# 02_-STLinkV2_1.net
KiCad netlist of a schematic drawn in Altium Designer
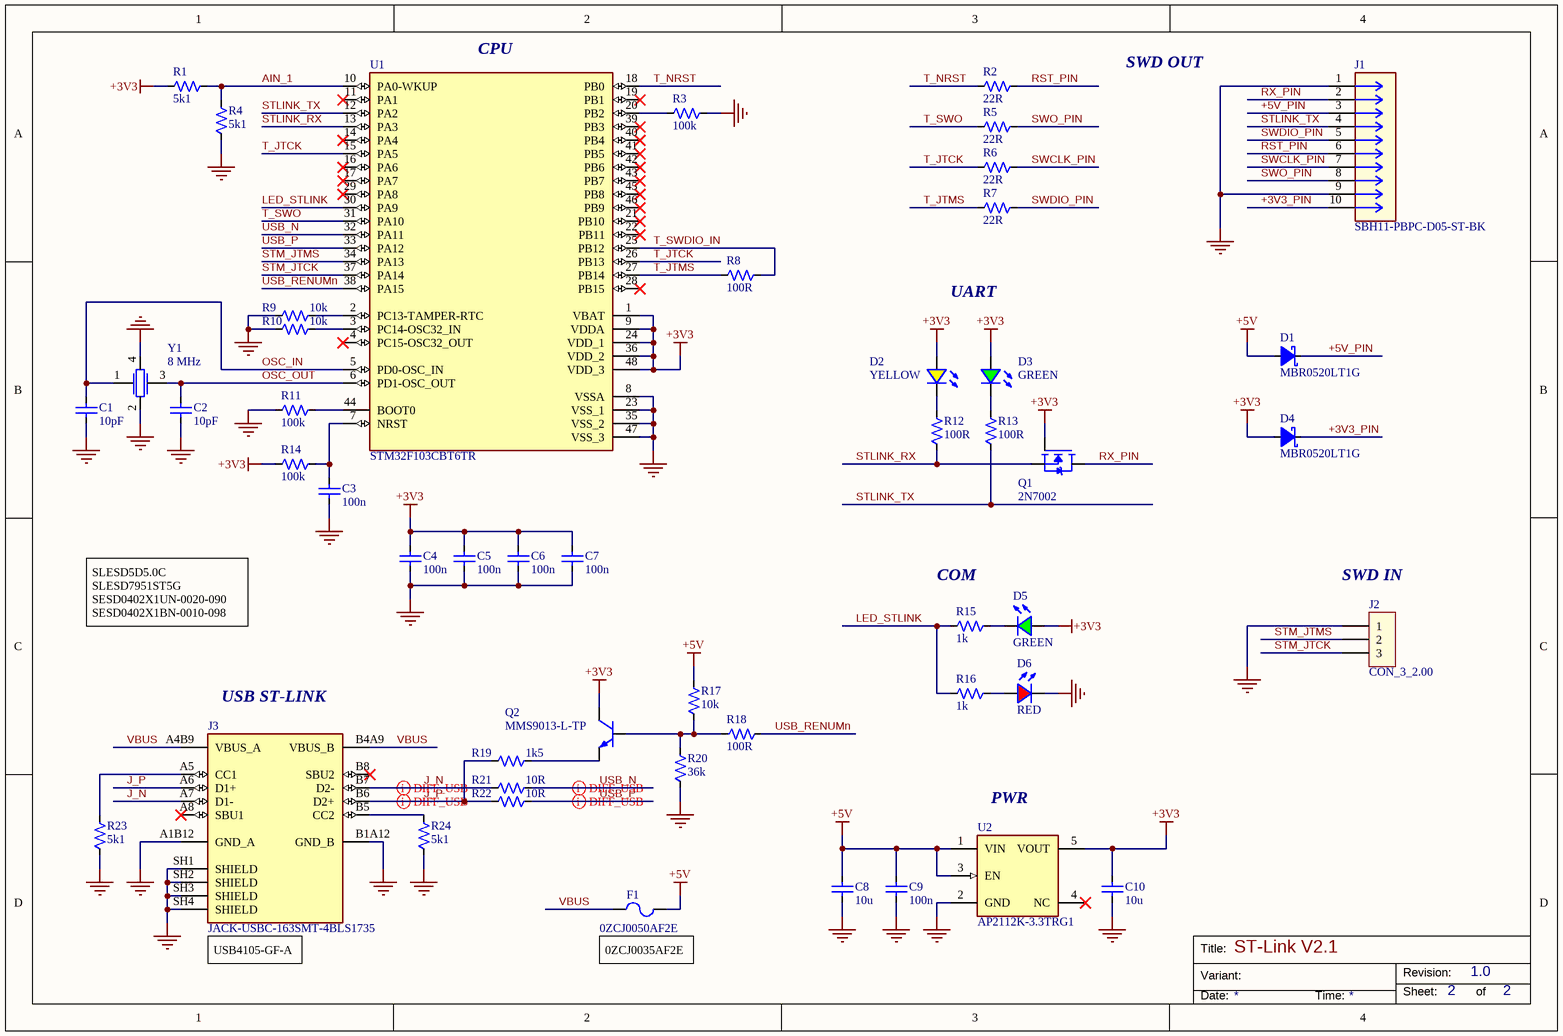
[diagram p0: [02]-STLinkV2_1.SchDoc]

(export (version "E")
  (design (tool "Eeschema 10.0.6"))
  (components
    (comp (ref "C1")
      (value "10pF")
      (footprint "CAPC1005X55N")
      (description "50V 10pF C0G ±5% 0402 Multilayer Ceramic Capacitors MLCC - SMD/SMT ROHS")
      (fields (field (name "TOLERANCE") "5%"))
      (libsource (lib "STLinkV2_1") (part "CAP_GCM1555C1H100JA16D"))
    )
    (comp (ref "C2")
      (value "10pF")
      (footprint "CAPC1005X55N")
      (description "50V 10pF C0G ±5% 0402 Multilayer Ceramic Capacitors MLCC - SMD/SMT ROHS")
      (fields (field (name "TOLERANCE") "5%"))
      (libsource (lib "STLinkV2_1") (part "CAP_GCM1555C1H100JA16D"))
    )
    (comp (ref "C3")
      (value "100n")
      (footprint "CAPC1005X55N")
      (description "50V 100nF X7R ±10% 0402 Multilayer Ceramic Capacitors MLCC - SMD/SMT ROHS")
      (fields (field (name "TOLERANCE") "10%"))
      (libsource (lib "STLinkV2_1") (part "CAP_GCM155R71H104KE02D"))
    )
    (comp (ref "C4")
      (value "100n")
      (footprint "CAPC1005X55N")
      (description "50V 100nF X7R ±10% 0402 Multilayer Ceramic Capacitors MLCC - SMD/SMT ROHS")
      (fields (field (name "TOLERANCE") "10%"))
      (libsource (lib "STLinkV2_1") (part "CAP_GCM155R71H104KE02D"))
    )
    (comp (ref "C5")
      (value "100n")
      (footprint "CAPC1005X55N")
      (description "50V 100nF X7R ±10% 0402 Multilayer Ceramic Capacitors MLCC - SMD/SMT ROHS")
      (fields (field (name "TOLERANCE") "10%"))
      (libsource (lib "STLinkV2_1") (part "CAP_GCM155R71H104KE02D"))
    )
    (comp (ref "C6")
      (value "100n")
      (footprint "CAPC1005X55N")
      (description "50V 100nF X7R ±10% 0402 Multilayer Ceramic Capacitors MLCC - SMD/SMT ROHS")
      (fields (field (name "TOLERANCE") "10%"))
      (libsource (lib "STLinkV2_1") (part "CAP_GCM155R71H104KE02D"))
    )
    (comp (ref "C7")
      (value "100n")
      (footprint "CAPC1005X55N")
      (description "50V 100nF X7R ±10% 0402 Multilayer Ceramic Capacitors MLCC - SMD/SMT ROHS")
      (fields (field (name "TOLERANCE") "10%"))
      (libsource (lib "STLinkV2_1") (part "CAP_GCM155R71H104KE02D"))
    )
    (comp (ref "C8")
      (value "10u")
      (footprint "CAPC0603(1608Metric)L")
      (description "10 µF ±20% 16V Ceramic Capacitor X6S 0603 (1608 Metric)")
      (fields (field (name "TOLERANCE") "20%") (field (name "VOLTAGE") "16V"))
      (libsource (lib "STLinkV2_1") (part "CAP_GRM188C81C106MA73D"))
    )
    (comp (ref "C9")
      (value "100n")
      (footprint "CAPC1005X55N")
      (description "50V 100nF X7R ±10% 0402 Multilayer Ceramic Capacitors MLCC - SMD/SMT ROHS")
      (fields (field (name "TOLERANCE") "10%"))
      (libsource (lib "STLinkV2_1") (part "CAP_GCM155R71H104KE02D"))
    )
    (comp (ref "C10")
      (value "10u")
      (footprint "CAPC0603(1608Metric)L")
      (description "10 µF ±20% 16V Ceramic Capacitor X6S 0603 (1608 Metric)")
      (fields (field (name "TOLERANCE") "20%") (field (name "VOLTAGE") "16V"))
      (libsource (lib "STLinkV2_1") (part "CAP_GRM188C81C106MA73D"))
    )
    (comp (ref "D1")
      (value "MBR0520LT1G")
      (footprint "SOD3716X135N")
      (description "Diode, Schottky Barrier, Vr 20V, If 0.5A, Pkg SOD-123, Vf 0.385V, Tj +125DEGC, Cs 5.5A")
      (libsource (lib "STLinkV2_1") (part "MBR0520LT1G"))
    )
    (comp (ref "D2")
      (value "YELLOW")
      (footprint "WL-SMCW_0603_150060xx75003")
      (description "Led, Yellow, 550Mcd, 595Nm Rohs Compliant: Yes")
      (libsource (lib "STLinkV2_1") (part "150060YS75003"))
    )
    (comp (ref "D3")
      (value "GREEN")
      (footprint "WL-SMCW_0603_150060xx75003")
      (description "Led, Bright Green, 100Mcd, 572Nm Rohs Compliant: Yes")
      (libsource (lib "STLinkV2_1") (part "150060VS75003"))
    )
    (comp (ref "D4")
      (value "MBR0520LT1G")
      (footprint "SOD3716X135N")
      (description "Diode, Schottky Barrier, Vr 20V, If 0.5A, Pkg SOD-123, Vf 0.385V, Tj +125DEGC, Cs 5.5A")
      (libsource (lib "STLinkV2_1") (part "MBR0520LT1G"))
    )
    (comp (ref "D5")
      (value "GREEN")
      (footprint "WL-SMCW_0603_150060xx75003")
      (description "Led, Bright Green, 100Mcd, 572Nm Rohs Compliant: Yes")
      (libsource (lib "STLinkV2_1") (part "150060VS75003"))
    )
    (comp (ref "D6")
      (value "RED")
      (description "SMT Mono-Color Chip LED Waterclear Advance WL-SMCW_0603_ADVANCE")
      (libsource (lib "STLinkV2_1") (part "150060RS75003"))
    )
    (comp (ref "F1")
      (value "0ZCJ0050AF2E")
      (footprint "0ZCJ_BEL")
      (description "Resettable Fuse, PPTC, 1206 (3216 Metric), 0ZCJ Series, 24 VDC, 500 mA, 1 A, 0.1 s")
      (libsource (lib "STLinkV2_1") (part "0ZCJ0050AF2E"))
    )
    (comp (ref "J1")
      (value "SBH11-PBPC-D05-ST-BK")
      (footprint "SULLINS_SBH11-PBPC-D05-ST-BK-H")
      (description "Conn Shrouded Header (4 Sides) HDR 10 POS 2.54mm Solder ST Top Entry Thru-Hole")
      (libsource (lib "STLinkV2_1") (part "SBH11-PBPC-D05-ST-BK"))
    )
    (comp (ref "J2")
      (value "CON_3_2.00")
      (footprint "Pin3")
      (libsource (lib "STLinkV2_1") (part "CON_3_2.00"))
    )
    (comp (ref "J3")
      (value "JACK-USBC-163SMT-4BLS1735")
      (footprint "JACK-USBC-163SMT-4BLS1735")
      (description "Usb Type C Jack IPX7 SMT")
      (libsource (lib "STLinkV2_1") (part "JACK-USBC-163SMT-4BLS1735"))
    )
    (comp (ref "Q1")
      (value "2N7002")
      (footprint "SOT23-3")
      (description "MOSFET N-CH 60V 300MA SOT23-3 N-Channel 60 V 300mA (Ta) 500mW (Ta) Surface Mount PG-SOT23")
      (libsource (lib "STLinkV2_1") (part "2N7002H6327XTSA2"))
    )
    (comp (ref "Q2")
      (value "MMS9013-L-TP")
      (footprint "SOT23-3")
      (description "Small Signal Bipolar Transistor, 0.5A I(C), 25V V(BR)CEO, 1-Element, NPN, Silicon")
      (libsource (lib "STLinkV2_1") (part "MMS9013-L-TP"))
    )
    (comp (ref "R1")
      (value "5k1")
      (footprint "RESC1005X37N")
      (description "Res Thick Film 0402 5.1K Ohm 1% 0.063W(1/16W) ±100ppm/°C Pad SMD T/R Automotive AEC-Q200")
      (fields (field (name "TOLERANCE") "1%"))
      (libsource (lib "STLinkV2_1") (part "RES_AC0402FR-135K1L"))
    )
    (comp (ref "R2")
      (value "22R")
      (footprint "RESC1005X37N")
      (description "125mW Thick Film Resistors ±100ppm/℃ ±1% 22Ω 0402 Chip Resistor - Surface Mount ROHS")
      (fields (field (name "TOLERANCE") "1%"))
      (libsource (lib "STLinkV2_1") (part "RES_AC0402FR-7W22RL"))
    )
    (comp (ref "R3")
      (value "100k")
      (footprint "RESC1005X37N")
      (description "Res Thick Film 0402 100K Ohm 1% 0.125W(1/8W) ±100ppm/°C Pad SMD T/R Automotive AEC-Q200")
      (fields (field (name "TOLERANCE") "1%"))
      (libsource (lib "STLinkV2_1") (part "RES_AC0402FR-7W100KL"))
    )
    (comp (ref "R4")
      (value "5k1")
      (footprint "RESC1005X37N")
      (description "Res Thick Film 0402 5.1K Ohm 1% 0.063W(1/16W) ±100ppm/°C Pad SMD T/R Automotive AEC-Q200")
      (fields (field (name "TOLERANCE") "1%"))
      (libsource (lib "STLinkV2_1") (part "RES_AC0402FR-135K1L"))
    )
    (comp (ref "R5")
      (value "22R")
      (footprint "RESC1005X37N")
      (description "125mW Thick Film Resistors ±100ppm/℃ ±1% 22Ω 0402 Chip Resistor - Surface Mount ROHS")
      (fields (field (name "TOLERANCE") "1%"))
      (libsource (lib "STLinkV2_1") (part "RES_AC0402FR-7W22RL"))
    )
    (comp (ref "R6")
      (value "22R")
      (footprint "RESC1005X37N")
      (description "125mW Thick Film Resistors ±100ppm/℃ ±1% 22Ω 0402 Chip Resistor - Surface Mount ROHS")
      (fields (field (name "TOLERANCE") "1%"))
      (libsource (lib "STLinkV2_1") (part "RES_AC0402FR-7W22RL"))
    )
    (comp (ref "R7")
      (value "22R")
      (footprint "RESC1005X37N")
      (description "125mW Thick Film Resistors ±100ppm/℃ ±1% 22Ω 0402 Chip Resistor - Surface Mount ROHS")
      (fields (field (name "TOLERANCE") "1%"))
      (libsource (lib "STLinkV2_1") (part "RES_AC0402FR-7W22RL"))
    )
    (comp (ref "R8")
      (value "100R")
      (footprint "RESC1005X37N")
      (description "Res Thick Film 0402 100 Ohm 1% 0.125W(1/8W) ±100ppm/C Pad SMD T/R Automotive AEC-Q200")
      (fields (field (name "TOLERANCE") "1%"))
      (libsource (lib "STLinkV2_1") (part "RES_AC0402FR-7W100RL"))
    )
    (comp (ref "R9")
      (value "10k")
      (footprint "RESC1005X37N")
      (description "Res Thick Film 0402 10K Ohm 1% 0.125W(1/8W) ±100ppm/C Pad SMD Automotive T/R")
      (fields (field (name "TOLERANCE") "1%"))
      (libsource (lib "STLinkV2_1") (part "RES_AC0402FR-7W10KL"))
    )
    (comp (ref "R10")
      (value "10k")
      (footprint "RESC1005X37N")
      (description "Res Thick Film 0402 10K Ohm 1% 0.125W(1/8W) ±100ppm/C Pad SMD Automotive T/R")
      (fields (field (name "TOLERANCE") "1%"))
      (libsource (lib "STLinkV2_1") (part "RES_AC0402FR-7W10KL"))
    )
    (comp (ref "R11")
      (value "100k")
      (footprint "RESC1005X37N")
      (description "Res Thick Film 0402 100K Ohm 1% 0.125W(1/8W) ±100ppm/°C Pad SMD T/R Automotive AEC-Q200")
      (fields (field (name "TOLERANCE") "1%"))
      (libsource (lib "STLinkV2_1") (part "RES_AC0402FR-7W100KL"))
    )
    (comp (ref "R12")
      (value "100R")
      (footprint "RESC1005X37N")
      (description "Res Thick Film 0402 100 Ohm 1% 0.125W(1/8W) ±100ppm/C Pad SMD T/R Automotive AEC-Q200")
      (fields (field (name "TOLERANCE") "1%"))
      (libsource (lib "STLinkV2_1") (part "RES_AC0402FR-7W100RL"))
    )
    (comp (ref "R13")
      (value "100R")
      (footprint "RESC1005X37N")
      (description "Res Thick Film 0402 100 Ohm 1% 0.125W(1/8W) ±100ppm/C Pad SMD T/R Automotive AEC-Q200")
      (fields (field (name "TOLERANCE") "1%"))
      (libsource (lib "STLinkV2_1") (part "RES_AC0402FR-7W100RL"))
    )
    (comp (ref "R14")
      (value "100k")
      (footprint "RESC1005X37N")
      (description "Res Thick Film 0402 100K Ohm 1% 0.125W(1/8W) ±100ppm/°C Pad SMD T/R Automotive AEC-Q200")
      (fields (field (name "TOLERANCE") "1%"))
      (libsource (lib "STLinkV2_1") (part "RES_AC0402FR-7W100KL"))
    )
    (comp (ref "R15")
      (value "1k")
      (footprint "RESC1005X37N")
      (description "Res Thick Film 0402 1K Ohm 1% 0.125W(1/8W) ±100ppm/C Pad SMD Automotive T/R")
      (fields (field (name "TOLERANCE") "1%"))
      (libsource (lib "STLinkV2_1") (part "RES_AC0402FR-7W1KL"))
    )
    (comp (ref "R16")
      (value "1k")
      (footprint "RESC1005X37N")
      (description "Res Thick Film 0402 1K Ohm 1% 0.125W(1/8W) ±100ppm/C Pad SMD Automotive T/R")
      (fields (field (name "TOLERANCE") "1%"))
      (libsource (lib "STLinkV2_1") (part "RES_AC0402FR-7W1KL"))
    )
    (comp (ref "R17")
      (value "10k")
      (footprint "RESC1005X37N")
      (description "Res Thick Film 0402 10K Ohm 1% 0.125W(1/8W) ±100ppm/C Pad SMD Automotive T/R")
      (fields (field (name "TOLERANCE") "1%"))
      (libsource (lib "STLinkV2_1") (part "RES_AC0402FR-7W10KL"))
    )
    (comp (ref "R18")
      (value "100R")
      (footprint "RESC1005X37N")
      (description "Res Thick Film 0402 100 Ohm 1% 0.125W(1/8W) ±100ppm/C Pad SMD T/R Automotive AEC-Q200")
      (fields (field (name "TOLERANCE") "1%"))
      (libsource (lib "STLinkV2_1") (part "RES_AC0402FR-7W100RL"))
    )
    (comp (ref "R19")
      (value "1k5")
      (footprint "RESC1005X37N")
      (fields (field (name "TOLERANCE") "1%"))
      (libsource (lib "STLinkV2_1") (part "RES_AC0402FR-7W1K5L"))
    )
    (comp (ref "R20")
      (value "36k")
      (footprint "RESC1005X37N")
      (description "Chip Resistor Automotive Grade Thick Film 0402 36kOhm 1% Paper T/R")
      (fields (field (name "TOLERANCE") "1%"))
      (libsource (lib "STLinkV2_1") (part "RES_AC0402FR-7W36KL"))
    )
    (comp (ref "R21")
      (value "10R")
      (footprint "RESC1005X37N")
      (description "Res Thick Film 0402 10 Ohm 1% 0.125W(1/8W) ±100ppm/C Pad SMD T/R Automotive AEC-Q200")
      (fields (field (name "TOLERANCE") "1%"))
      (libsource (lib "STLinkV2_1") (part "RES_AC0402FR-7W10RL"))
    )
    (comp (ref "R22")
      (value "10R")
      (footprint "RESC1005X37N")
      (description "Res Thick Film 0402 10 Ohm 1% 0.125W(1/8W) ±100ppm/C Pad SMD T/R Automotive AEC-Q200")
      (fields (field (name "TOLERANCE") "1%"))
      (libsource (lib "STLinkV2_1") (part "RES_AC0402FR-7W10RL"))
    )
    (comp (ref "R23")
      (value "5k1")
      (footprint "RESC1005X37N")
      (description "Res Thick Film 0402 5.1K Ohm 1% 0.063W(1/16W) ±100ppm/°C Pad SMD T/R Automotive AEC-Q200")
      (fields (field (name "TOLERANCE") "1%"))
      (libsource (lib "STLinkV2_1") (part "RES_AC0402FR-135K1L"))
    )
    (comp (ref "R24")
      (value "5k1")
      (footprint "RESC1005X37N")
      (description "Res Thick Film 0402 5.1K Ohm 1% 0.063W(1/16W) ±100ppm/°C Pad SMD T/R Automotive AEC-Q200")
      (fields (field (name "TOLERANCE") "1%"))
      (libsource (lib "STLinkV2_1") (part "RES_AC0402FR-135K1L"))
    )
    (comp (ref "U1")
      (value "STM32F103CBT6TR")
      (footprint "QFP50P900X900X160-48N")
      (description "MCU 32-bit STM32F1 ARM Cortex M3 RISC 128KB Flash 2.5V/3.3V 48-Pin LQFP T/R")
      (libsource (lib "STLinkV2_1") (part "STM32F103CBT6TR"))
    )
    (comp (ref "U2")
      (value "AP2112K-3.3TRG1")
      (footprint "SOT95P285X140-5N")
      (description "AP2112 Series 0.6 A 3.3 V Fixed Output SMT LDO Linear Regulator - SOT23-5")
      (libsource (lib "STLinkV2_1") (part "AP2112K-3.3TRG1"))
    )
    (comp (ref "Y1")
      (value "8 MHz")
      (footprint "XTAL_C3E-8.000-8-1015-R")
      (description "CRYSTAL 8.0000MHZ 10PF SMD")
      (fields (field (name "MFG") "ECS Inc.") (field (name "MFG PART NUMBER") "ECS-80-10-33-CKM-TR3"))
      (libsource (lib "STLinkV2_1") (part "Y_ECS-80-10-33-CKM-TR3"))
    )
  )
  (nets
    (net (code "1") (name "+3V3") (class "Default")
      (node (ref "C10") (pin "2") (pinfunction "2_2") (pintype "passive"))
      (node (ref "C4") (pin "1") (pinfunction "1_1") (pintype "passive"))
      (node (ref "C5") (pin "1") (pinfunction "1_1") (pintype "passive"))
      (node (ref "C6") (pin "1") (pinfunction "1_1") (pintype "passive"))
      (node (ref "C7") (pin "1") (pinfunction "1_1") (pintype "passive"))
      (node (ref "D2") (pin "1") (pinfunction "POS_1") (pintype "passive"))
      (node (ref "D3") (pin "1") (pinfunction "POS_1") (pintype "passive"))
      (node (ref "D4") (pin "1") (pinfunction "A_1") (pintype "passive"))
      (node (ref "D5") (pin "1") (pinfunction "POS_1") (pintype "passive"))
      (node (ref "Q1") (pin "1") (pinfunction "G_1") (pintype "passive"))
      (node (ref "Q2") (pin "3") (pinfunction "C_3") (pintype "passive"))
      (node (ref "R1") (pin "2") (pinfunction "2_2") (pintype "passive"))
      (node (ref "R14") (pin "2") (pinfunction "2_2") (pintype "passive"))
      (node (ref "U1") (pin "1") (pinfunction "VBAT_1") (pintype "power_in"))
      (node (ref "U1") (pin "24") (pinfunction "VDD_1_24") (pintype "power_in"))
      (node (ref "U1") (pin "36") (pinfunction "VDD_2_36") (pintype "power_in"))
      (node (ref "U1") (pin "48") (pinfunction "VDD_3_48") (pintype "power_in"))
      (node (ref "U1") (pin "9") (pinfunction "VDDA_9") (pintype "power_in"))
      (node (ref "U2") (pin "5") (pinfunction "VOUT_5") (pintype "power_in"))
    )
    (net (code "2") (name "+5V") (class "Default")
      (node (ref "C8") (pin "2") (pinfunction "2_2") (pintype "passive"))
      (node (ref "C9") (pin "1") (pinfunction "1_1") (pintype "passive"))
      (node (ref "D1") (pin "1") (pinfunction "A_1") (pintype "passive"))
      (node (ref "F1") (pin "2") (pinfunction "2_2") (pintype "passive"))
      (node (ref "R17") (pin "1") (pinfunction "1_1") (pintype "passive"))
      (node (ref "U2") (pin "1") (pinfunction "VIN_1") (pintype "power_in"))
      (node (ref "U2") (pin "3") (pinfunction "EN_3") (pintype "input"))
    )
    (net (code "3") (name "/+3V3_PIN") (class "Default")
      (node (ref "D4") (pin "2") (pinfunction "K_2") (pintype "passive"))
      (node (ref "J1") (pin "10") (pinfunction "10_10") (pintype "passive"))
    )
    (net (code "4") (name "/+5V_PIN") (class "Default")
      (node (ref "D1") (pin "2") (pinfunction "K_2") (pintype "passive"))
      (node (ref "J1") (pin "3") (pinfunction "3_3") (pintype "passive"))
    )
    (net (code "5") (name "/AIN_1") (class "Default")
      (node (ref "R1") (pin "1") (pinfunction "1_1") (pintype "passive"))
      (node (ref "R4") (pin "1") (pinfunction "1_1") (pintype "passive"))
      (node (ref "U1") (pin "10") (pinfunction "PA0-WKUP_10") (pintype "bidirectional"))
    )
    (net (code "6") (name "/J_N") (class "Default")
      (node (ref "J3") (pin "A7") (pinfunction "D1-_A7") (pintype "bidirectional"))
      (node (ref "J3") (pin "B7") (pinfunction "D2-_B7") (pintype "bidirectional"))
      (node (ref "R21") (pin "2") (pinfunction "2_2") (pintype "passive"))
    )
    (net (code "7") (name "/J_P") (class "Default")
      (node (ref "J3") (pin "A6") (pinfunction "D1+_A6") (pintype "bidirectional"))
      (node (ref "J3") (pin "B6") (pinfunction "D2+_B6") (pintype "bidirectional"))
      (node (ref "R19") (pin "2") (pinfunction "2_2") (pintype "passive"))
      (node (ref "R22") (pin "2") (pinfunction "2_2") (pintype "passive"))
    )
    (net (code "8") (name "/LED_STLINK") (class "Default")
      (node (ref "R15") (pin "2") (pinfunction "2_2") (pintype "passive"))
      (node (ref "R16") (pin "2") (pinfunction "2_2") (pintype "passive"))
      (node (ref "U1") (pin "30") (pinfunction "PA9_30") (pintype "bidirectional"))
    )
    (net (code "9") (name "/OSC_IN") (class "Default")
      (node (ref "C1") (pin "2") (pinfunction "2_2") (pintype "passive"))
      (node (ref "U1") (pin "5") (pinfunction "PD0-OSC_IN_5") (pintype "bidirectional"))
      (node (ref "Y1") (pin "1") (pinfunction "1_1") (pintype "passive"))
    )
    (net (code "10") (name "/OSC_OUT") (class "Default")
      (node (ref "C2") (pin "2") (pinfunction "2_2") (pintype "passive"))
      (node (ref "U1") (pin "6") (pinfunction "PD1-OSC_OUT_6") (pintype "bidirectional"))
      (node (ref "Y1") (pin "3") (pinfunction "2_3") (pintype "passive"))
    )
    (net (code "11") (name "/RST_PIN") (class "Default")
      (node (ref "J1") (pin "6") (pinfunction "6_6") (pintype "passive"))
      (node (ref "R2") (pin "1") (pinfunction "1_1") (pintype "passive"))
    )
    (net (code "12") (name "/RX_PIN") (class "Default")
      (node (ref "J1") (pin "2") (pinfunction "2_2") (pintype "passive"))
      (node (ref "Q1") (pin "3") (pinfunction "D_3") (pintype "passive"))
    )
    (net (code "13") (name "/STLINK_RX") (class "Default")
      (node (ref "Q1") (pin "2") (pinfunction "S_2") (pintype "passive"))
      (node (ref "R12") (pin "2") (pinfunction "2_2") (pintype "passive"))
      (node (ref "U1") (pin "13") (pinfunction "PA3_13") (pintype "bidirectional"))
    )
    (net (code "14") (name "/STLINK_TX") (class "Default")
      (node (ref "J1") (pin "4") (pinfunction "4_4") (pintype "passive"))
      (node (ref "R13") (pin "2") (pinfunction "2_2") (pintype "passive"))
      (node (ref "U1") (pin "12") (pinfunction "PA2_12") (pintype "bidirectional"))
    )
    (net (code "15") (name "/STM_JTCK") (class "Default")
      (node (ref "J2") (pin "3") (pinfunction "3_3") (pintype "passive"))
      (node (ref "U1") (pin "37") (pinfunction "PA14_37") (pintype "bidirectional"))
    )
    (net (code "16") (name "/STM_JTMS") (class "Default")
      (node (ref "J2") (pin "2") (pinfunction "2_2") (pintype "passive"))
      (node (ref "U1") (pin "34") (pinfunction "PA13_34") (pintype "bidirectional"))
    )
    (net (code "17") (name "/SWCLK_PIN") (class "Default")
      (node (ref "J1") (pin "7") (pinfunction "7_7") (pintype "passive"))
      (node (ref "R6") (pin "1") (pinfunction "1_1") (pintype "passive"))
    )
    (net (code "18") (name "/SWDIO_PIN") (class "Default")
      (node (ref "J1") (pin "5") (pinfunction "5_5") (pintype "passive"))
      (node (ref "R7") (pin "1") (pinfunction "1_1") (pintype "passive"))
    )
    (net (code "19") (name "/SWO_PIN") (class "Default")
      (node (ref "J1") (pin "8") (pinfunction "8_8") (pintype "passive"))
      (node (ref "R5") (pin "1") (pinfunction "1_1") (pintype "passive"))
    )
    (net (code "20") (name "/T_JTCK") (class "Default")
      (node (ref "R6") (pin "2") (pinfunction "2_2") (pintype "passive"))
      (node (ref "U1") (pin "15") (pinfunction "PA5_15") (pintype "bidirectional"))
      (node (ref "U1") (pin "26") (pinfunction "PB13_26") (pintype "bidirectional"))
    )
    (net (code "21") (name "/T_JTMS") (class "Default")
      (node (ref "R7") (pin "2") (pinfunction "2_2") (pintype "passive"))
      (node (ref "R8") (pin "2") (pinfunction "2_2") (pintype "passive"))
      (node (ref "U1") (pin "27") (pinfunction "PB14_27") (pintype "bidirectional"))
    )
    (net (code "22") (name "/T_NRST") (class "Default")
      (node (ref "R2") (pin "2") (pinfunction "2_2") (pintype "passive"))
      (node (ref "U1") (pin "18") (pinfunction "PB0_18") (pintype "bidirectional"))
    )
    (net (code "23") (name "/T_SWDIO_IN") (class "Default")
      (node (ref "R8") (pin "1") (pinfunction "1_1") (pintype "passive"))
      (node (ref "U1") (pin "25") (pinfunction "PB12_25") (pintype "bidirectional"))
    )
    (net (code "24") (name "/T_SWO") (class "Default")
      (node (ref "R5") (pin "2") (pinfunction "2_2") (pintype "passive"))
      (node (ref "U1") (pin "31") (pinfunction "PA10_31") (pintype "bidirectional"))
    )
    (net (code "25") (name "/USB_N") (class "Default")
      (node (ref "R21") (pin "1") (pinfunction "1_1") (pintype "passive"))
      (node (ref "U1") (pin "32") (pinfunction "PA11_32") (pintype "bidirectional"))
    )
    (net (code "26") (name "/USB_P") (class "Default")
      (node (ref "R22") (pin "1") (pinfunction "1_1") (pintype "passive"))
      (node (ref "U1") (pin "33") (pinfunction "PA12_33") (pintype "bidirectional"))
    )
    (net (code "27") (name "/USB_RENUMn") (class "Default")
      (node (ref "R18") (pin "2") (pinfunction "2_2") (pintype "passive"))
      (node (ref "U1") (pin "38") (pinfunction "PA15_38") (pintype "bidirectional"))
    )
    (net (code "28") (name "/VBUS") (class "Default")
      (node (ref "F1") (pin "1") (pinfunction "1_1") (pintype "passive"))
      (node (ref "J3") (pin "A4B9") (pinfunction "VBUS_A_A4B9") (pintype "power_in"))
      (node (ref "J3") (pin "B4A9") (pinfunction "VBUS_B_B4A9") (pintype "power_in"))
    )
    (net (code "29") (name "GND") (class "Default")
      (node (ref "C1") (pin "1") (pinfunction "1_1") (pintype "passive"))
      (node (ref "C10") (pin "1") (pinfunction "1_1") (pintype "passive"))
      (node (ref "C2") (pin "1") (pinfunction "1_1") (pintype "passive"))
      (node (ref "C3") (pin "2") (pinfunction "2_2") (pintype "passive"))
      (node (ref "C4") (pin "2") (pinfunction "2_2") (pintype "passive"))
      (node (ref "C5") (pin "2") (pinfunction "2_2") (pintype "passive"))
      (node (ref "C6") (pin "2") (pinfunction "2_2") (pintype "passive"))
      (node (ref "C7") (pin "2") (pinfunction "2_2") (pintype "passive"))
      (node (ref "C8") (pin "1") (pinfunction "1_1") (pintype "passive"))
      (node (ref "C9") (pin "2") (pinfunction "2_2") (pintype "passive"))
      (node (ref "D6") (pin "2") (pinfunction "NEG_2") (pintype "passive"))
      (node (ref "J1") (pin "1") (pinfunction "1_1") (pintype "passive"))
      (node (ref "J1") (pin "9") (pinfunction "9_9") (pintype "passive"))
      (node (ref "J2") (pin "1") (pinfunction "1_1") (pintype "passive"))
      (node (ref "J3") (pin "A1B12") (pinfunction "GND_A_A1B12") (pintype "power_in"))
      (node (ref "J3") (pin "B1A12") (pinfunction "GND_B_B1A12") (pintype "power_in"))
      (node (ref "J3") (pin "SH1") (pinfunction "SHIELD_SH1") (pintype "passive"))
      (node (ref "J3") (pin "SH2") (pinfunction "SHIELD_SH2") (pintype "passive"))
      (node (ref "J3") (pin "SH3") (pinfunction "SHIELD_SH3") (pintype "passive"))
      (node (ref "J3") (pin "SH4") (pinfunction "SHIELD_SH4") (pintype "passive"))
      (node (ref "R10") (pin "2") (pinfunction "2_2") (pintype "passive"))
      (node (ref "R11") (pin "2") (pinfunction "2_2") (pintype "passive"))
      (node (ref "R20") (pin "2") (pinfunction "2_2") (pintype "passive"))
      (node (ref "R23") (pin "2") (pinfunction "2_2") (pintype "passive"))
      (node (ref "R24") (pin "2") (pinfunction "2_2") (pintype "passive"))
      (node (ref "R3") (pin "1") (pinfunction "1_1") (pintype "passive"))
      (node (ref "R4") (pin "2") (pinfunction "2_2") (pintype "passive"))
      (node (ref "R9") (pin "2") (pinfunction "2_2") (pintype "passive"))
      (node (ref "U1") (pin "23") (pinfunction "VSS_1_23") (pintype "power_in"))
      (node (ref "U1") (pin "35") (pinfunction "VSS_2_35") (pintype "power_in"))
      (node (ref "U1") (pin "47") (pinfunction "VSS_3_47") (pintype "power_in"))
      (node (ref "U1") (pin "8") (pinfunction "VSSA_8") (pintype "power_in"))
      (node (ref "U2") (pin "2") (pinfunction "GND_2") (pintype "power_in"))
      (node (ref "Y1") (pin "2") (pinfunction "GND_2") (pintype "power_in"))
      (node (ref "Y1") (pin "4") (pinfunction "GND_4") (pintype "power_in"))
    )
    (net (code "30") (name "Net-(D2-NEG)") (class "Default")
      (node (ref "D2") (pin "2") (pinfunction "NEG_2") (pintype "passive"))
      (node (ref "R12") (pin "1") (pinfunction "1_1") (pintype "passive"))
    )
    (net (code "31") (name "Net-(D3-NEG)") (class "Default")
      (node (ref "D3") (pin "2") (pinfunction "NEG_2") (pintype "passive"))
      (node (ref "R13") (pin "1") (pinfunction "1_1") (pintype "passive"))
    )
    (net (code "32") (name "Net-(D5-NEG)") (class "Default")
      (node (ref "D5") (pin "2") (pinfunction "NEG_2") (pintype "passive"))
      (node (ref "R15") (pin "1") (pinfunction "1_1") (pintype "passive"))
    )
    (net (code "33") (name "Net-(D6-POS)") (class "Default")
      (node (ref "D6") (pin "1") (pinfunction "POS_1") (pintype "passive"))
      (node (ref "R16") (pin "1") (pinfunction "1_1") (pintype "passive"))
    )
    (net (code "34") (name "Net-(J3-CC1)") (class "Default")
      (node (ref "J3") (pin "A5") (pinfunction "CC1_A5") (pintype "bidirectional"))
      (node (ref "R23") (pin "1") (pinfunction "1_1") (pintype "passive"))
    )
    (net (code "35") (name "Net-(J3-CC2)") (class "Default")
      (node (ref "J3") (pin "B5") (pinfunction "CC2_B5") (pintype "bidirectional"))
      (node (ref "R24") (pin "1") (pinfunction "1_1") (pintype "passive"))
    )
    (net (code "36") (name "Net-(Q2-B)") (class "Default")
      (node (ref "Q2") (pin "1") (pinfunction "B_1") (pintype "passive"))
      (node (ref "R17") (pin "2") (pinfunction "2_2") (pintype "passive"))
      (node (ref "R18") (pin "1") (pinfunction "1_1") (pintype "passive"))
      (node (ref "R20") (pin "1") (pinfunction "1_1") (pintype "passive"))
    )
    (net (code "37") (name "Net-(Q2-E)") (class "Default")
      (node (ref "Q2") (pin "2") (pinfunction "E_2") (pintype "passive"))
      (node (ref "R19") (pin "1") (pinfunction "1_1") (pintype "passive"))
    )
    (net (code "38") (name "Net-(U1-BOOT0)") (class "Default")
      (node (ref "R11") (pin "1") (pinfunction "1_1") (pintype "passive"))
      (node (ref "U1") (pin "44") (pinfunction "BOOT0_44") (pintype "passive"))
    )
    (net (code "39") (name "Net-(U1-NRST)") (class "Default")
      (node (ref "C3") (pin "1") (pinfunction "1_1") (pintype "passive"))
      (node (ref "R14") (pin "1") (pinfunction "1_1") (pintype "passive"))
      (node (ref "U1") (pin "7") (pinfunction "NRST_7") (pintype "bidirectional"))
    )
    (net (code "40") (name "Net-(U1-PB2)") (class "Default")
      (node (ref "R3") (pin "2") (pinfunction "2_2") (pintype "passive"))
      (node (ref "U1") (pin "20") (pinfunction "PB2_20") (pintype "bidirectional"))
    )
    (net (code "41") (name "Net-(U1-PC13-TAMPER-RTC)") (class "Default")
      (node (ref "R9") (pin "1") (pinfunction "1_1") (pintype "passive"))
      (node (ref "U1") (pin "2") (pinfunction "PC13-TAMPER-RTC_2") (pintype "bidirectional"))
    )
    (net (code "42") (name "Net-(U1-PC14-OSC32_IN)") (class "Default")
      (node (ref "R10") (pin "1") (pinfunction "1_1") (pintype "passive"))
      (node (ref "U1") (pin "3") (pinfunction "PC14-OSC32_IN_3") (pintype "bidirectional"))
    )
    (net (code "43") (name "unconnected-(J3-SBU1-PadA8)") (class "Default")
      (node (ref "J3") (pin "A8") (pinfunction "SBU1_A8") (pintype "bidirectional+no_connect"))
    )
    (net (code "44") (name "unconnected-(J3-SBU2-PadB8)") (class "Default")
      (node (ref "J3") (pin "B8") (pinfunction "SBU2_B8") (pintype "bidirectional+no_connect"))
    )
    (net (code "45") (name "unconnected-(U1-PA1-Pad11)") (class "Default")
      (node (ref "U1") (pin "11") (pinfunction "PA1_11") (pintype "bidirectional+no_connect"))
    )
    (net (code "46") (name "unconnected-(U1-PA4-Pad14)") (class "Default")
      (node (ref "U1") (pin "14") (pinfunction "PA4_14") (pintype "bidirectional+no_connect"))
    )
    (net (code "47") (name "unconnected-(U1-PA6-Pad16)") (class "Default")
      (node (ref "U1") (pin "16") (pinfunction "PA6_16") (pintype "bidirectional+no_connect"))
    )
    (net (code "48") (name "unconnected-(U1-PA7-Pad17)") (class "Default")
      (node (ref "U1") (pin "17") (pinfunction "PA7_17") (pintype "bidirectional+no_connect"))
    )
    (net (code "49") (name "unconnected-(U1-PA8-Pad29)") (class "Default")
      (node (ref "U1") (pin "29") (pinfunction "PA8_29") (pintype "bidirectional+no_connect"))
    )
    (net (code "50") (name "unconnected-(U1-PB1-Pad19)") (class "Default")
      (node (ref "U1") (pin "19") (pinfunction "PB1_19") (pintype "bidirectional+no_connect"))
    )
    (net (code "51") (name "unconnected-(U1-PB3-Pad39)") (class "Default")
      (node (ref "U1") (pin "39") (pinfunction "PB3_39") (pintype "bidirectional+no_connect"))
    )
    (net (code "52") (name "unconnected-(U1-PB4-Pad40)") (class "Default")
      (node (ref "U1") (pin "40") (pinfunction "PB4_40") (pintype "bidirectional+no_connect"))
    )
    (net (code "53") (name "unconnected-(U1-PB5-Pad41)") (class "Default")
      (node (ref "U1") (pin "41") (pinfunction "PB5_41") (pintype "bidirectional+no_connect"))
    )
    (net (code "54") (name "unconnected-(U1-PB6-Pad42)") (class "Default")
      (node (ref "U1") (pin "42") (pinfunction "PB6_42") (pintype "bidirectional+no_connect"))
    )
    (net (code "55") (name "unconnected-(U1-PB7-Pad43)") (class "Default")
      (node (ref "U1") (pin "43") (pinfunction "PB7_43") (pintype "bidirectional+no_connect"))
    )
    (net (code "56") (name "unconnected-(U1-PB8-Pad45)") (class "Default")
      (node (ref "U1") (pin "45") (pinfunction "PB8_45") (pintype "bidirectional+no_connect"))
    )
    (net (code "57") (name "unconnected-(U1-PB9-Pad46)") (class "Default")
      (node (ref "U1") (pin "46") (pinfunction "PB9_46") (pintype "bidirectional+no_connect"))
    )
    (net (code "58") (name "unconnected-(U1-PB10-Pad21)") (class "Default")
      (node (ref "U1") (pin "21") (pinfunction "PB10_21") (pintype "bidirectional+no_connect"))
    )
    (net (code "59") (name "unconnected-(U1-PB11-Pad22)") (class "Default")
      (node (ref "U1") (pin "22") (pinfunction "PB11_22") (pintype "bidirectional+no_connect"))
    )
    (net (code "60") (name "unconnected-(U1-PB15-Pad28)") (class "Default")
      (node (ref "U1") (pin "28") (pinfunction "PB15_28") (pintype "bidirectional+no_connect"))
    )
    (net (code "61") (name "unconnected-(U1-PC15-OSC32_OUT-Pad4)") (class "Default")
      (node (ref "U1") (pin "4") (pinfunction "PC15-OSC32_OUT_4") (pintype "bidirectional+no_connect"))
    )
    (net (code "62") (name "unconnected-(U2-NC-Pad4)") (class "Default")
      (node (ref "U2") (pin "4") (pinfunction "NC_4") (pintype "passive+no_connect"))
    )
  )
)
